# console-dat.net
KiCad netlist of a schematic drawn in EAGLE
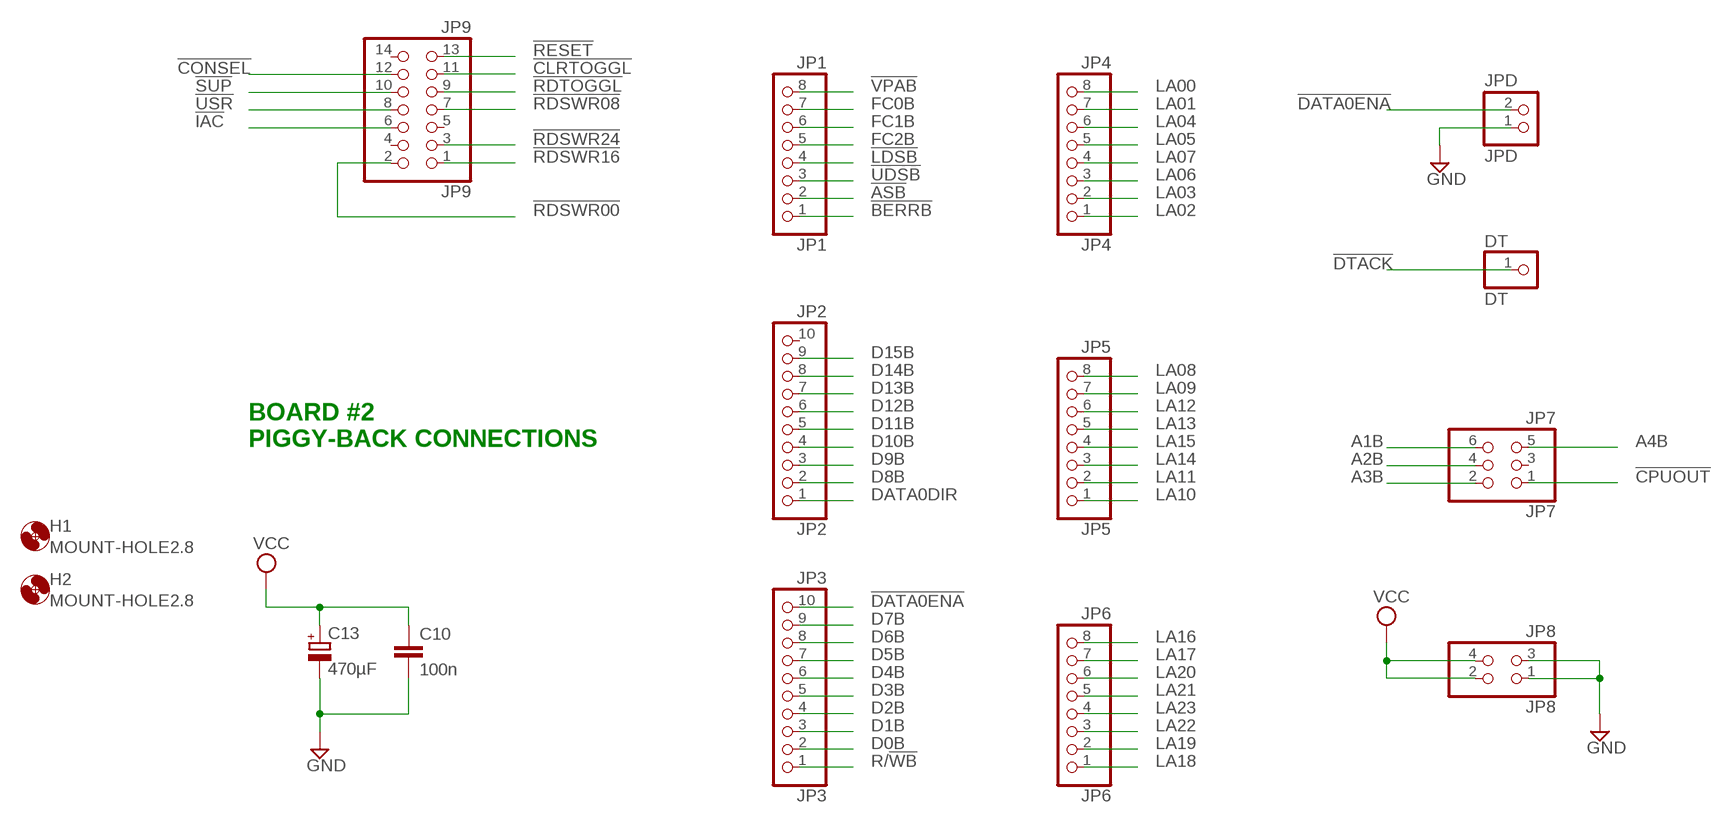
[diagram p0: schematic, sheet 1]
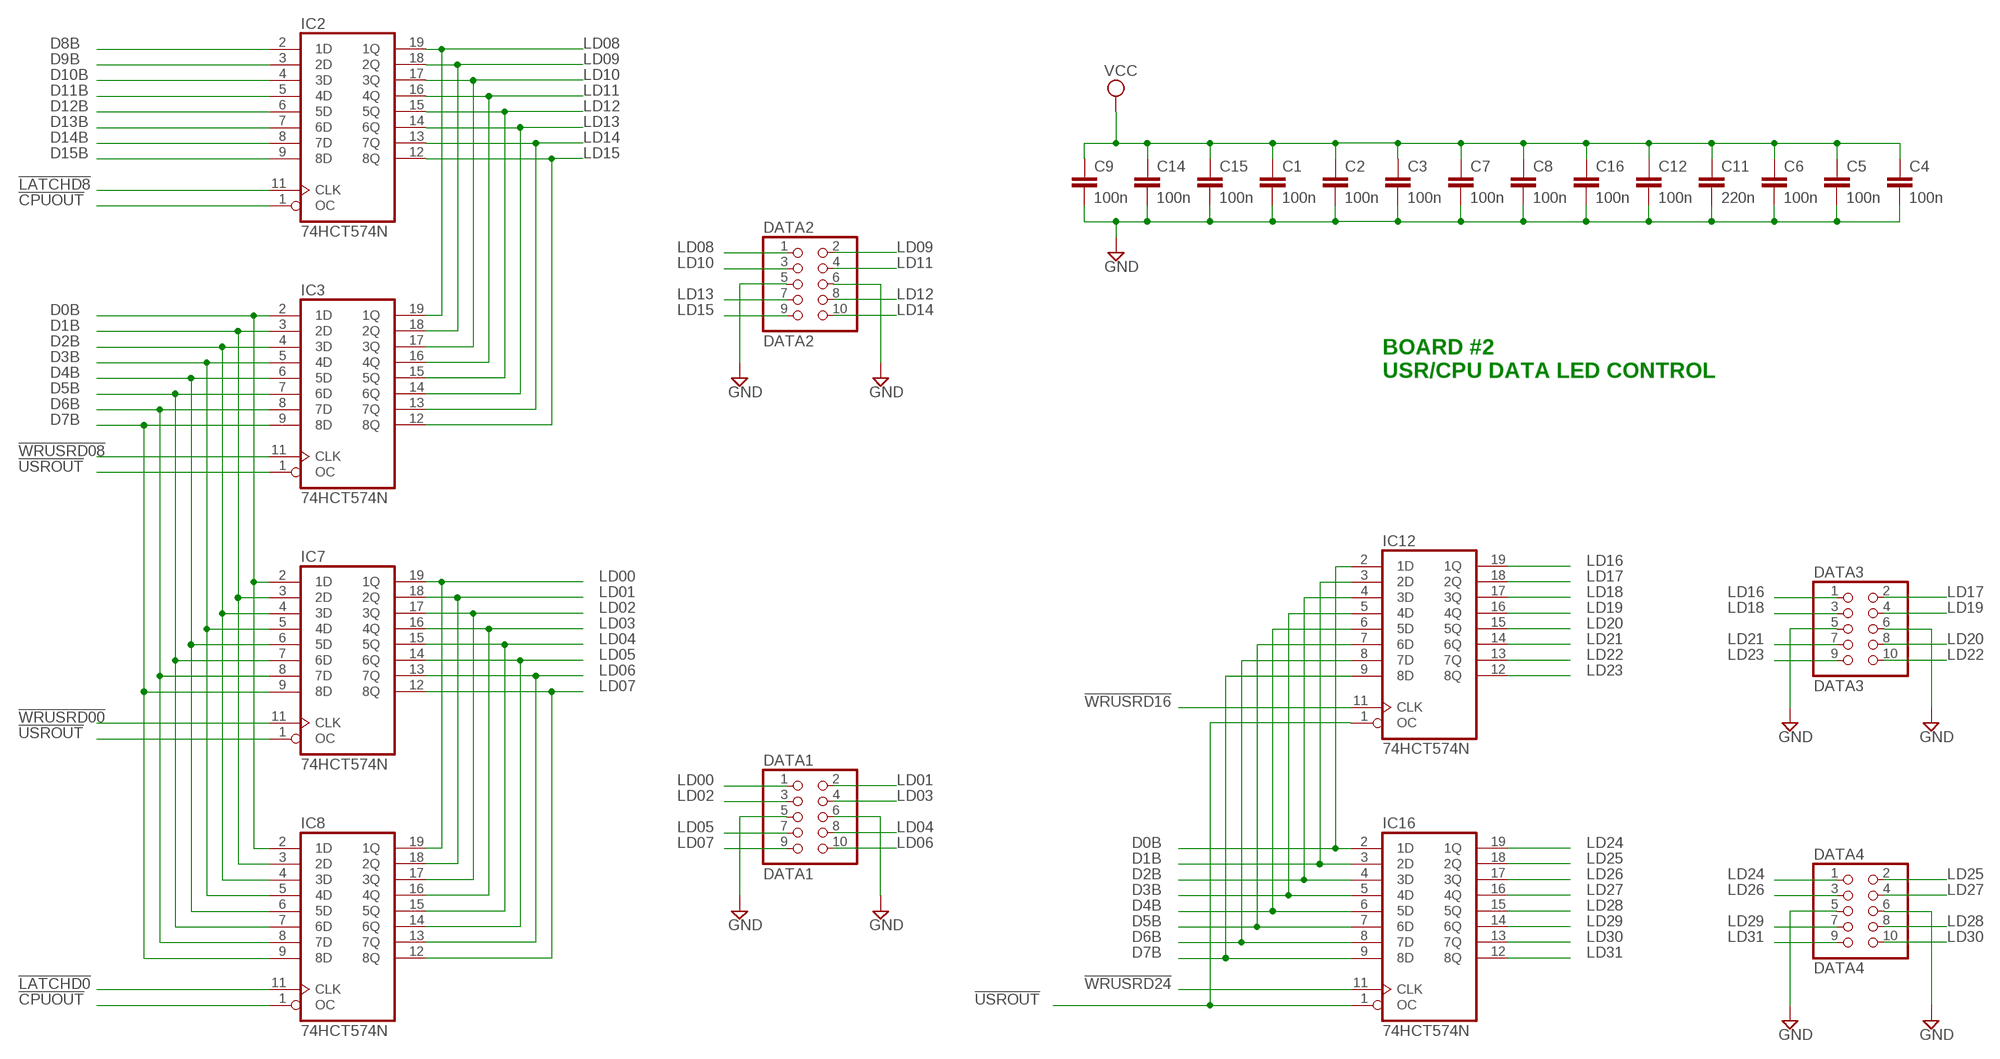
[diagram p1: schematic, sheet 2]
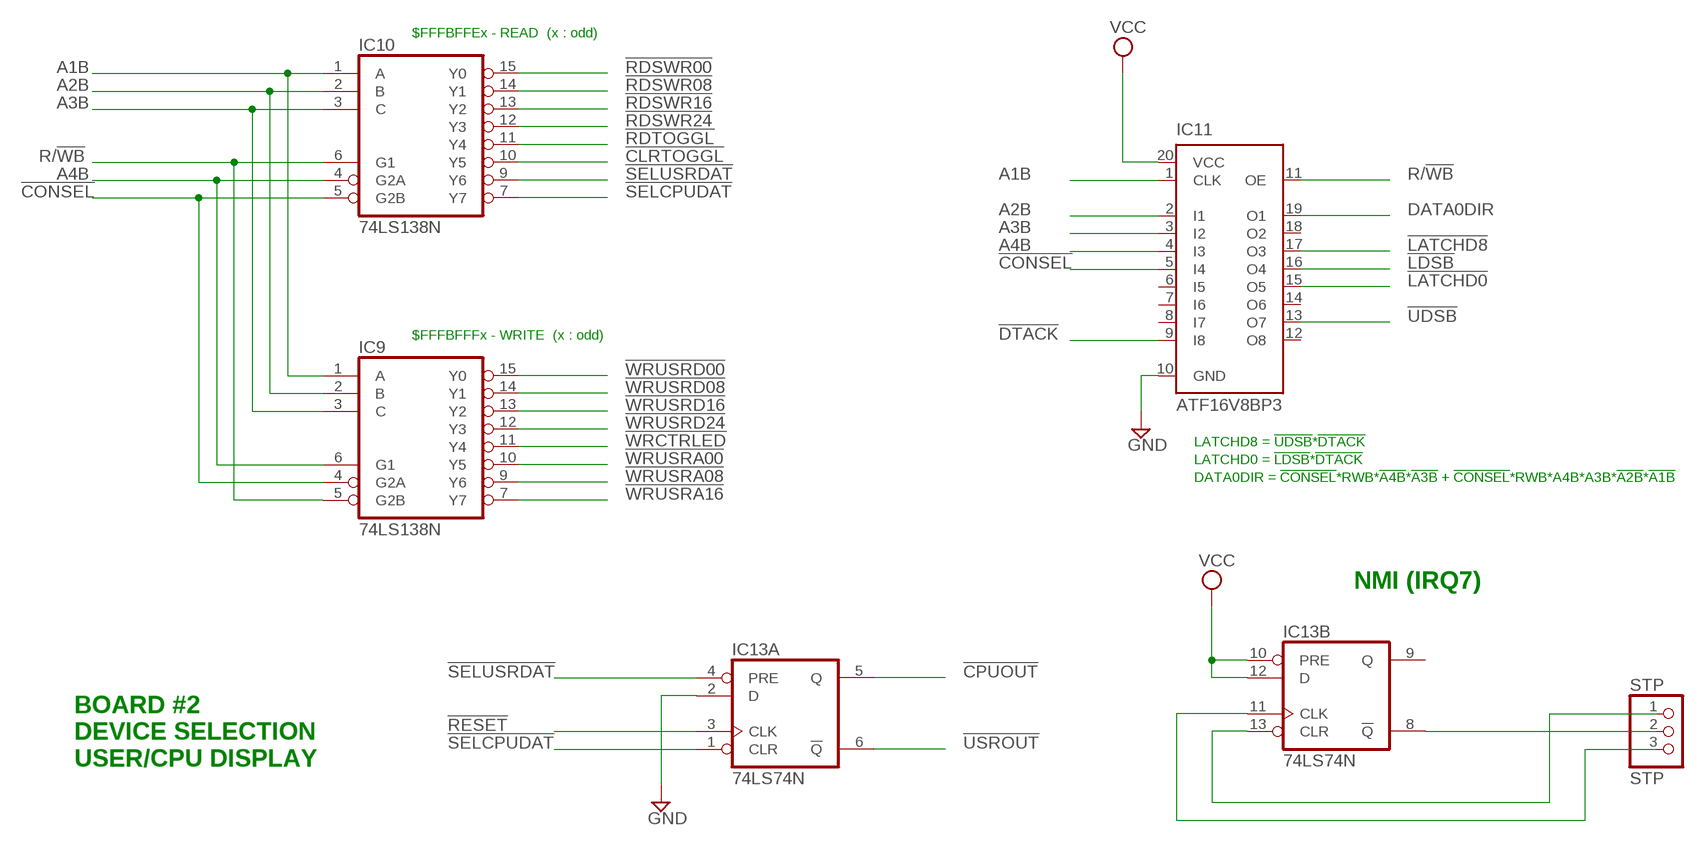
[diagram p2: schematic, sheet 3]
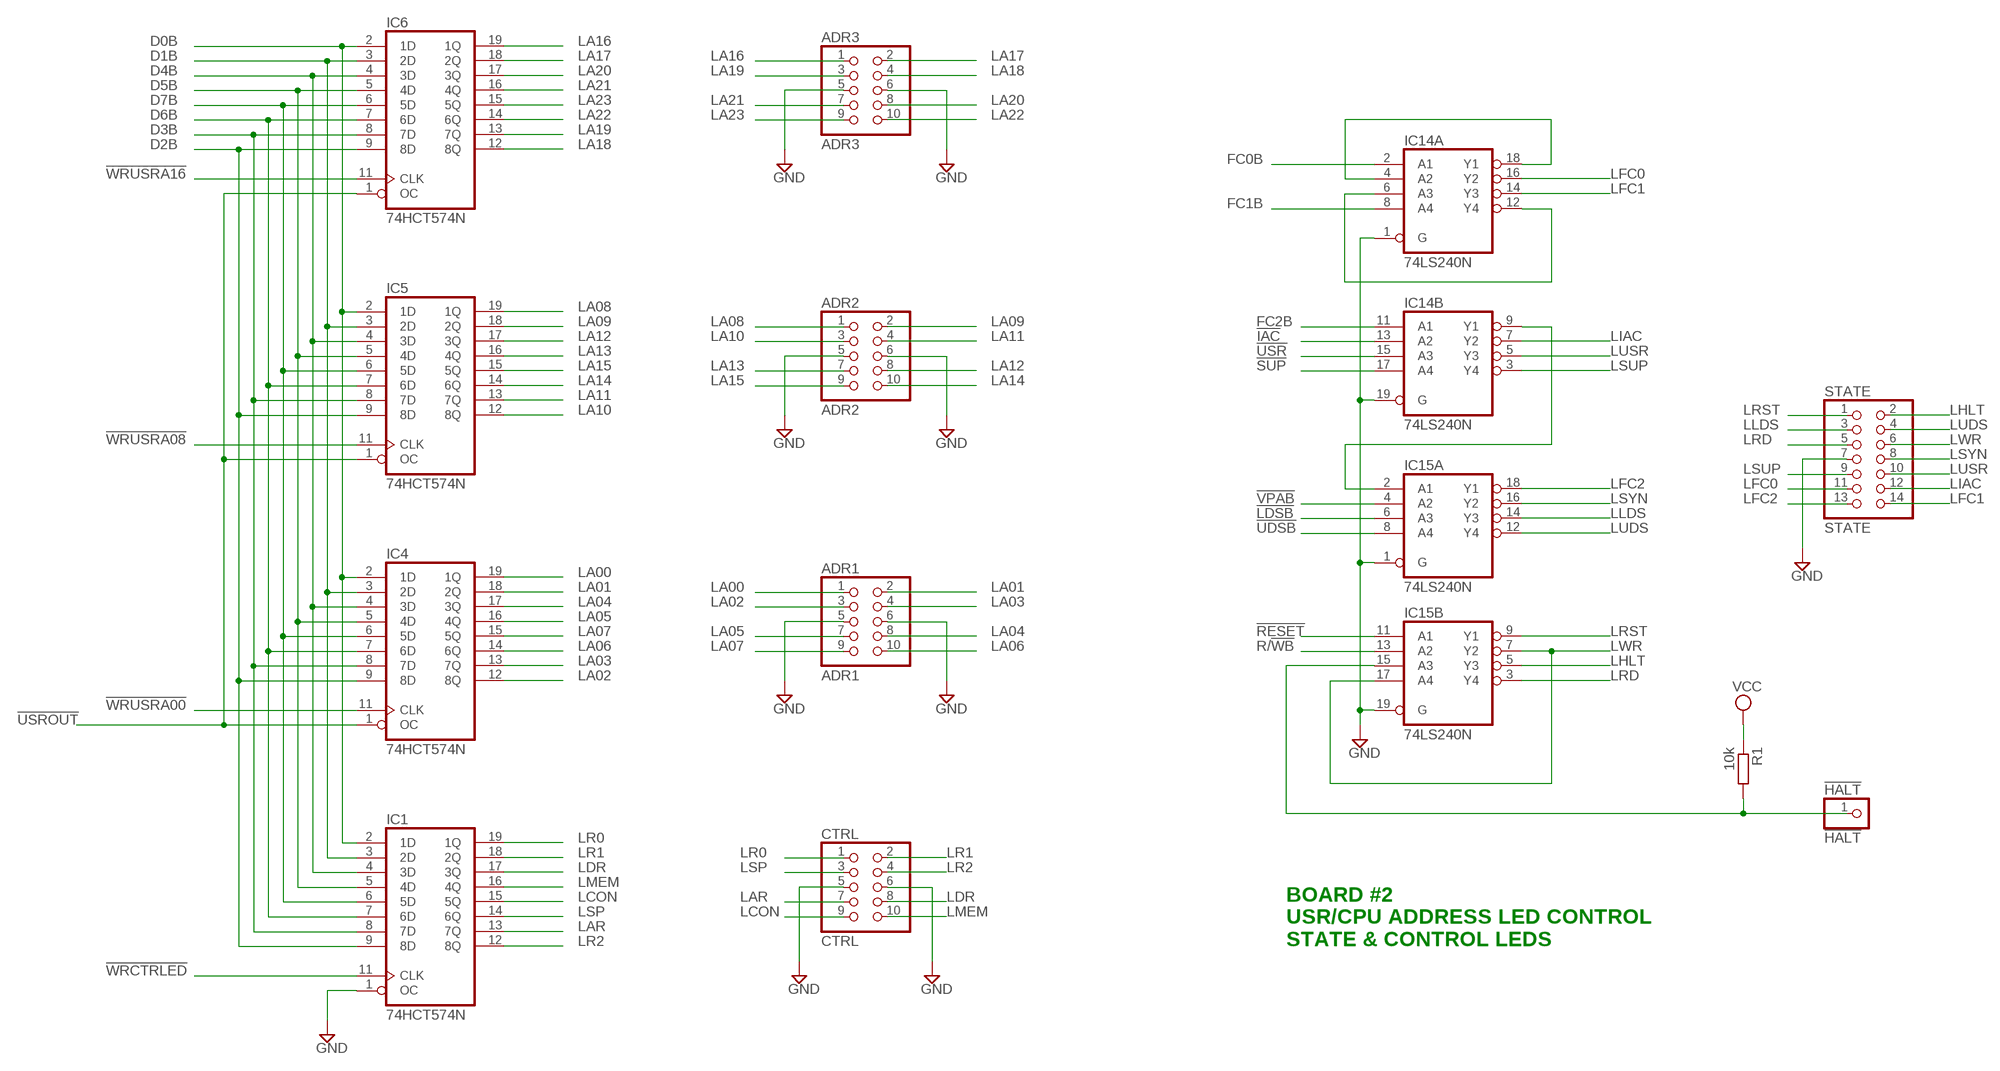
[diagram p3: schematic, sheet 4]

(export (version "E")
  (design (tool "Eeschema 10.0.6"))
  (components
    (comp (ref "IC9")
      (value "74LS138N")
      (footprint "eagle-import:DIL16")
      (libsource (lib "eagle-import") (part "74138NLS"))
    )
    (comp (ref "IC10")
      (value "74LS138N")
      (footprint "eagle-import:DIL16")
      (libsource (lib "eagle-import") (part "74138NLS"))
    )
    (comp (ref "IC11")
      (value "ATF16V8BP3")
      (footprint "eagle-import:DIL20")
      (fields (field (name "MPN") "ATF16V8CZ-15PU"))
      (libsource (lib "eagle-import") (part "ATF16V8BP3"))
    )
    (comp (ref "IC13")
      (value "74LS74N")
      (footprint "eagle-import:DIL14")
      (libsource (lib "eagle-import") (part "7474NLS"))
    )
    (comp (ref "STP")
      (value "STP")
      (footprint "eagle-import:1X03")
      (libsource (lib "eagle-import") (part "PINHD-1X3"))
    )
    (comp (ref "C10")
      (value "100n")
      (footprint "eagle-import:C025-024X044")
      (libsource (lib "eagle-import") (part "C-EU025-024X044"))
    )
    (comp (ref "C13")
      (value "470µF")
      (footprint "eagle-import:E2,5-7")
      (libsource (lib "eagle-import") (part "CPOL-EUE2.5-7"))
    )
    (comp (ref "DT")
      (value "DT")
      (footprint "eagle-import:1X01")
      (libsource (lib "eagle-import") (part "PINHD-1X1"))
    )
    (comp (ref "H1")
      (value "MOUNT-HOLE2.8")
      (footprint "eagle-import:2,8")
      (libsource (lib "eagle-import") (part "MOUNT-HOLE2.8"))
    )
    (comp (ref "H2")
      (value "MOUNT-HOLE2.8")
      (footprint "eagle-import:2,8")
      (libsource (lib "eagle-import") (part "MOUNT-HOLE2.8"))
    )
    (comp (ref "JP1")
      (value "JP1")
      (footprint "eagle-import:1X08")
      (libsource (lib "eagle-import") (part "PINHD-1X8"))
    )
    (comp (ref "JP2")
      (value "JP2")
      (footprint "eagle-import:1X10")
      (libsource (lib "eagle-import") (part "PINHD-1X10"))
    )
    (comp (ref "JP3")
      (value "JP3")
      (footprint "eagle-import:1X10")
      (libsource (lib "eagle-import") (part "PINHD-1X10"))
    )
    (comp (ref "JP4")
      (value "JP4")
      (footprint "eagle-import:1X08")
      (libsource (lib "eagle-import") (part "PINHD-1X8"))
    )
    (comp (ref "JP5")
      (value "JP5")
      (footprint "eagle-import:1X08")
      (libsource (lib "eagle-import") (part "PINHD-1X8"))
    )
    (comp (ref "JP6")
      (value "JP6")
      (footprint "eagle-import:1X08")
      (libsource (lib "eagle-import") (part "PINHD-1X8"))
    )
    (comp (ref "JP7")
      (value "JP7")
      (footprint "eagle-import:2X03")
      (libsource (lib "eagle-import") (part "PINHD-2X3"))
    )
    (comp (ref "JP8")
      (value "JP8")
      (footprint "eagle-import:2X02")
      (libsource (lib "eagle-import") (part "PINHD-2X2"))
    )
    (comp (ref "JP9")
      (value "JP9")
      (footprint "eagle-import:2X07")
      (libsource (lib "eagle-import") (part "PINHD-2X7"))
    )
    (comp (ref "JPD")
      (value "JPD")
      (footprint "eagle-import:1X02")
      (libsource (lib "eagle-import") (part "PINHD-1X2"))
    )
    (comp (ref "C1")
      (value "100n")
      (footprint "eagle-import:C025-024X044")
      (libsource (lib "eagle-import") (part "C-EU025-024X044"))
    )
    (comp (ref "C2")
      (value "100n")
      (footprint "eagle-import:C025-024X044")
      (libsource (lib "eagle-import") (part "C-EU025-024X044"))
    )
    (comp (ref "C3")
      (value "100n")
      (footprint "eagle-import:C025-024X044")
      (libsource (lib "eagle-import") (part "C-EU025-024X044"))
    )
    (comp (ref "C4")
      (value "100n")
      (footprint "eagle-import:C025-024X044")
      (libsource (lib "eagle-import") (part "C-EU025-024X044"))
    )
    (comp (ref "C5")
      (value "100n")
      (footprint "eagle-import:C025-024X044")
      (libsource (lib "eagle-import") (part "C-EU025-024X044"))
    )
    (comp (ref "C6")
      (value "100n")
      (footprint "eagle-import:C025-024X044")
      (libsource (lib "eagle-import") (part "C-EU025-024X044"))
    )
    (comp (ref "C7")
      (value "100n")
      (footprint "eagle-import:C025-024X044")
      (libsource (lib "eagle-import") (part "C-EU025-024X044"))
    )
    (comp (ref "C8")
      (value "100n")
      (footprint "eagle-import:C025-024X044")
      (libsource (lib "eagle-import") (part "C-EU025-024X044"))
    )
    (comp (ref "C9")
      (value "100n")
      (footprint "eagle-import:C025-024X044")
      (libsource (lib "eagle-import") (part "C-EU025-024X044"))
    )
    (comp (ref "C11")
      (value "220n")
      (footprint "eagle-import:C025-024X044")
      (libsource (lib "eagle-import") (part "C-EU025-024X044"))
    )
    (comp (ref "C12")
      (value "100n")
      (footprint "eagle-import:C025-024X044")
      (libsource (lib "eagle-import") (part "C-EU025-024X044"))
    )
    (comp (ref "C14")
      (value "100n")
      (footprint "eagle-import:C025-024X044")
      (libsource (lib "eagle-import") (part "C-EU025-024X044"))
    )
    (comp (ref "C15")
      (value "100n")
      (footprint "eagle-import:C025-024X044")
      (libsource (lib "eagle-import") (part "C-EU025-024X044"))
    )
    (comp (ref "C16")
      (value "100n")
      (footprint "eagle-import:C025-024X044")
      (libsource (lib "eagle-import") (part "C-EU025-024X044"))
    )
    (comp (ref "DATA1")
      (value "DATA1")
      (footprint "eagle-import:2X05")
      (libsource (lib "eagle-import") (part "PINHD-2X5"))
    )
    (comp (ref "DATA2")
      (value "DATA2")
      (footprint "eagle-import:2X05")
      (libsource (lib "eagle-import") (part "PINHD-2X5"))
    )
    (comp (ref "DATA3")
      (value "DATA3")
      (footprint "eagle-import:2X05")
      (libsource (lib "eagle-import") (part "PINHD-2X5"))
    )
    (comp (ref "DATA4")
      (value "DATA4")
      (footprint "eagle-import:2X05")
      (libsource (lib "eagle-import") (part "PINHD-2X5"))
    )
    (comp (ref "IC2")
      (value "74HCT574N")
      (footprint "eagle-import:DIL20")
      (libsource (lib "eagle-import") (part "74574NHCT"))
    )
    (comp (ref "IC3")
      (value "74HCT574N")
      (footprint "eagle-import:DIL20")
      (libsource (lib "eagle-import") (part "74574NHCT"))
    )
    (comp (ref "IC7")
      (value "74HCT574N")
      (footprint "eagle-import:DIL20")
      (libsource (lib "eagle-import") (part "74574NHCT"))
    )
    (comp (ref "IC8")
      (value "74HCT574N")
      (footprint "eagle-import:DIL20")
      (libsource (lib "eagle-import") (part "74574NHCT"))
    )
    (comp (ref "IC12")
      (value "74HCT574N")
      (footprint "eagle-import:DIL20")
      (libsource (lib "eagle-import") (part "74574NHCT"))
    )
    (comp (ref "IC16")
      (value "74HCT574N")
      (footprint "eagle-import:DIL20")
      (libsource (lib "eagle-import") (part "74574NHCT"))
    )
    (comp (ref "!HALT")
      (value "!HALT")
      (footprint "eagle-import:1X01")
      (libsource (lib "eagle-import") (part "PINHD-1X1"))
    )
    (comp (ref "ADR1")
      (value "ADR1")
      (footprint "eagle-import:2X05")
      (libsource (lib "eagle-import") (part "PINHD-2X5"))
    )
    (comp (ref "ADR2")
      (value "ADR2")
      (footprint "eagle-import:2X05")
      (libsource (lib "eagle-import") (part "PINHD-2X5"))
    )
    (comp (ref "ADR3")
      (value "ADR3")
      (footprint "eagle-import:2X05")
      (libsource (lib "eagle-import") (part "PINHD-2X5"))
    )
    (comp (ref "CTRL")
      (value "CTRL")
      (footprint "eagle-import:2X05")
      (libsource (lib "eagle-import") (part "PINHD-2X5"))
    )
    (comp (ref "IC1")
      (value "74HCT574N")
      (footprint "eagle-import:DIL20")
      (libsource (lib "eagle-import") (part "74574NHCT"))
    )
    (comp (ref "IC4")
      (value "74HCT574N")
      (footprint "eagle-import:DIL20")
      (libsource (lib "eagle-import") (part "74574NHCT"))
    )
    (comp (ref "IC5")
      (value "74HCT574N")
      (footprint "eagle-import:DIL20")
      (libsource (lib "eagle-import") (part "74574NHCT"))
    )
    (comp (ref "IC6")
      (value "74HCT574N")
      (footprint "eagle-import:DIL20")
      (libsource (lib "eagle-import") (part "74574NHCT"))
    )
    (comp (ref "IC14")
      (value "74LS240N")
      (footprint "eagle-import:DIL20")
      (libsource (lib "eagle-import") (part "74240NLS"))
    )
    (comp (ref "IC15")
      (value "74LS240N")
      (footprint "eagle-import:DIL20")
      (libsource (lib "eagle-import") (part "74240NLS"))
    )
    (comp (ref "R1")
      (value "10k")
      (footprint "eagle-import:0204_7")
      (libsource (lib "eagle-import") (part "R-EU_0204/7"))
    )
    (comp (ref "STATE")
      (value "STATE")
      (footprint "eagle-import:2X07")
      (libsource (lib "eagle-import") (part "PINHD-2X7"))
    )
  )
  (nets
    (net (code "1") (name "A1B") (class "Default")
      (node (ref "IC10") (pin "1") (pinfunction "A_1") (pintype "input"))
      (node (ref "IC11") (pin "1") (pinfunction "CLK_1") (pintype "input"))
      (node (ref "IC9") (pin "1") (pinfunction "A_1") (pintype "input"))
      (node (ref "JP7") (pin "6") (pinfunction "6_6") (pintype "passive"))
    )
    (net (code "2") (name "A2B") (class "Default")
      (node (ref "IC10") (pin "2") (pinfunction "B_2") (pintype "input"))
      (node (ref "IC11") (pin "2") (pinfunction "I1_2") (pintype "input"))
      (node (ref "IC9") (pin "2") (pinfunction "B_2") (pintype "input"))
      (node (ref "JP7") (pin "4") (pinfunction "4_4") (pintype "passive"))
    )
    (net (code "3") (name "A3B") (class "Default")
      (node (ref "IC10") (pin "3") (pinfunction "C_3") (pintype "input"))
      (node (ref "IC11") (pin "3") (pinfunction "I2_3") (pintype "input"))
      (node (ref "IC9") (pin "3") (pinfunction "C_3") (pintype "input"))
      (node (ref "JP7") (pin "2") (pinfunction "2_2") (pintype "passive"))
    )
    (net (code "4") (name "A4B") (class "Default")
      (node (ref "IC10") (pin "4") (pinfunction "G2A_4") (pintype "input"))
      (node (ref "IC11") (pin "4") (pinfunction "I3_4") (pintype "input"))
      (node (ref "IC9") (pin "6") (pinfunction "G1_6") (pintype "input"))
      (node (ref "JP7") (pin "5") (pinfunction "5_5") (pintype "passive"))
    )
    (net (code "5") (name "D0B") (class "Default")
      (node (ref "IC1") (pin "2") (pinfunction "1D_2") (pintype "input"))
      (node (ref "IC12") (pin "2") (pinfunction "1D_2") (pintype "input"))
      (node (ref "IC16") (pin "2") (pinfunction "1D_2") (pintype "input"))
      (node (ref "IC3") (pin "2") (pinfunction "1D_2") (pintype "input"))
      (node (ref "IC4") (pin "2") (pinfunction "1D_2") (pintype "input"))
      (node (ref "IC5") (pin "2") (pinfunction "1D_2") (pintype "input"))
      (node (ref "IC6") (pin "2") (pinfunction "1D_2") (pintype "input"))
      (node (ref "IC7") (pin "2") (pinfunction "1D_2") (pintype "input"))
      (node (ref "IC8") (pin "2") (pinfunction "1D_2") (pintype "input"))
      (node (ref "JP3") (pin "2") (pinfunction "2_2") (pintype "passive"))
    )
    (net (code "6") (name "D1B") (class "Default")
      (node (ref "IC1") (pin "3") (pinfunction "2D_3") (pintype "input"))
      (node (ref "IC12") (pin "3") (pinfunction "2D_3") (pintype "input"))
      (node (ref "IC16") (pin "3") (pinfunction "2D_3") (pintype "input"))
      (node (ref "IC3") (pin "3") (pinfunction "2D_3") (pintype "input"))
      (node (ref "IC4") (pin "3") (pinfunction "2D_3") (pintype "input"))
      (node (ref "IC5") (pin "3") (pinfunction "2D_3") (pintype "input"))
      (node (ref "IC6") (pin "3") (pinfunction "2D_3") (pintype "input"))
      (node (ref "IC7") (pin "3") (pinfunction "2D_3") (pintype "input"))
      (node (ref "IC8") (pin "3") (pinfunction "2D_3") (pintype "input"))
      (node (ref "JP3") (pin "3") (pinfunction "3_3") (pintype "passive"))
    )
    (net (code "7") (name "D2B") (class "Default")
      (node (ref "IC1") (pin "9") (pinfunction "8D_9") (pintype "input"))
      (node (ref "IC12") (pin "4") (pinfunction "3D_4") (pintype "input"))
      (node (ref "IC16") (pin "4") (pinfunction "3D_4") (pintype "input"))
      (node (ref "IC3") (pin "4") (pinfunction "3D_4") (pintype "input"))
      (node (ref "IC4") (pin "9") (pinfunction "8D_9") (pintype "input"))
      (node (ref "IC5") (pin "9") (pinfunction "8D_9") (pintype "input"))
      (node (ref "IC6") (pin "9") (pinfunction "8D_9") (pintype "input"))
      (node (ref "IC7") (pin "4") (pinfunction "3D_4") (pintype "input"))
      (node (ref "IC8") (pin "4") (pinfunction "3D_4") (pintype "input"))
      (node (ref "JP3") (pin "4") (pinfunction "4_4") (pintype "passive"))
    )
    (net (code "8") (name "D3B") (class "Default")
      (node (ref "IC1") (pin "8") (pinfunction "7D_8") (pintype "input"))
      (node (ref "IC12") (pin "5") (pinfunction "4D_5") (pintype "input"))
      (node (ref "IC16") (pin "5") (pinfunction "4D_5") (pintype "input"))
      (node (ref "IC3") (pin "5") (pinfunction "4D_5") (pintype "input"))
      (node (ref "IC4") (pin "8") (pinfunction "7D_8") (pintype "input"))
      (node (ref "IC5") (pin "8") (pinfunction "7D_8") (pintype "input"))
      (node (ref "IC6") (pin "8") (pinfunction "7D_8") (pintype "input"))
      (node (ref "IC7") (pin "5") (pinfunction "4D_5") (pintype "input"))
      (node (ref "IC8") (pin "5") (pinfunction "4D_5") (pintype "input"))
      (node (ref "JP3") (pin "5") (pinfunction "5_5") (pintype "passive"))
    )
    (net (code "9") (name "D4B") (class "Default")
      (node (ref "IC1") (pin "4") (pinfunction "3D_4") (pintype "input"))
      (node (ref "IC12") (pin "6") (pinfunction "5D_6") (pintype "input"))
      (node (ref "IC16") (pin "6") (pinfunction "5D_6") (pintype "input"))
      (node (ref "IC3") (pin "6") (pinfunction "5D_6") (pintype "input"))
      (node (ref "IC4") (pin "4") (pinfunction "3D_4") (pintype "input"))
      (node (ref "IC5") (pin "4") (pinfunction "3D_4") (pintype "input"))
      (node (ref "IC6") (pin "4") (pinfunction "3D_4") (pintype "input"))
      (node (ref "IC7") (pin "6") (pinfunction "5D_6") (pintype "input"))
      (node (ref "IC8") (pin "6") (pinfunction "5D_6") (pintype "input"))
      (node (ref "JP3") (pin "6") (pinfunction "6_6") (pintype "passive"))
    )
    (net (code "10") (name "D5B") (class "Default")
      (node (ref "IC1") (pin "5") (pinfunction "4D_5") (pintype "input"))
      (node (ref "IC12") (pin "7") (pinfunction "6D_7") (pintype "input"))
      (node (ref "IC16") (pin "7") (pinfunction "6D_7") (pintype "input"))
      (node (ref "IC3") (pin "7") (pinfunction "6D_7") (pintype "input"))
      (node (ref "IC4") (pin "5") (pinfunction "4D_5") (pintype "input"))
      (node (ref "IC5") (pin "5") (pinfunction "4D_5") (pintype "input"))
      (node (ref "IC6") (pin "5") (pinfunction "4D_5") (pintype "input"))
      (node (ref "IC7") (pin "7") (pinfunction "6D_7") (pintype "input"))
      (node (ref "IC8") (pin "7") (pinfunction "6D_7") (pintype "input"))
      (node (ref "JP3") (pin "7") (pinfunction "7_7") (pintype "passive"))
    )
    (net (code "11") (name "D6B") (class "Default")
      (node (ref "IC1") (pin "7") (pinfunction "6D_7") (pintype "input"))
      (node (ref "IC12") (pin "8") (pinfunction "7D_8") (pintype "input"))
      (node (ref "IC16") (pin "8") (pinfunction "7D_8") (pintype "input"))
      (node (ref "IC3") (pin "8") (pinfunction "7D_8") (pintype "input"))
      (node (ref "IC4") (pin "7") (pinfunction "6D_7") (pintype "input"))
      (node (ref "IC5") (pin "7") (pinfunction "6D_7") (pintype "input"))
      (node (ref "IC6") (pin "7") (pinfunction "6D_7") (pintype "input"))
      (node (ref "IC7") (pin "8") (pinfunction "7D_8") (pintype "input"))
      (node (ref "IC8") (pin "8") (pinfunction "7D_8") (pintype "input"))
      (node (ref "JP3") (pin "8") (pinfunction "8_8") (pintype "passive"))
    )
    (net (code "12") (name "D7B") (class "Default")
      (node (ref "IC1") (pin "6") (pinfunction "5D_6") (pintype "input"))
      (node (ref "IC12") (pin "9") (pinfunction "8D_9") (pintype "input"))
      (node (ref "IC16") (pin "9") (pinfunction "8D_9") (pintype "input"))
      (node (ref "IC3") (pin "9") (pinfunction "8D_9") (pintype "input"))
      (node (ref "IC4") (pin "6") (pinfunction "5D_6") (pintype "input"))
      (node (ref "IC5") (pin "6") (pinfunction "5D_6") (pintype "input"))
      (node (ref "IC6") (pin "6") (pinfunction "5D_6") (pintype "input"))
      (node (ref "IC7") (pin "9") (pinfunction "8D_9") (pintype "input"))
      (node (ref "IC8") (pin "9") (pinfunction "8D_9") (pintype "input"))
      (node (ref "JP3") (pin "9") (pinfunction "9_9") (pintype "passive"))
    )
    (net (code "13") (name "D8B") (class "Default")
      (node (ref "IC2") (pin "2") (pinfunction "1D_2") (pintype "input"))
      (node (ref "JP2") (pin "2") (pinfunction "2_2") (pintype "passive"))
    )
    (net (code "14") (name "D9B") (class "Default")
      (node (ref "IC2") (pin "3") (pinfunction "2D_3") (pintype "input"))
      (node (ref "JP2") (pin "3") (pinfunction "3_3") (pintype "passive"))
    )
    (net (code "15") (name "D10B") (class "Default")
      (node (ref "IC2") (pin "4") (pinfunction "3D_4") (pintype "input"))
      (node (ref "JP2") (pin "4") (pinfunction "4_4") (pintype "passive"))
    )
    (net (code "16") (name "D11B") (class "Default")
      (node (ref "IC2") (pin "5") (pinfunction "4D_5") (pintype "input"))
      (node (ref "JP2") (pin "5") (pinfunction "5_5") (pintype "passive"))
    )
    (net (code "17") (name "D12B") (class "Default")
      (node (ref "IC2") (pin "6") (pinfunction "5D_6") (pintype "input"))
      (node (ref "JP2") (pin "6") (pinfunction "6_6") (pintype "passive"))
    )
    (net (code "18") (name "D13B") (class "Default")
      (node (ref "IC2") (pin "7") (pinfunction "6D_7") (pintype "input"))
      (node (ref "JP2") (pin "7") (pinfunction "7_7") (pintype "passive"))
    )
    (net (code "19") (name "D14B") (class "Default")
      (node (ref "IC2") (pin "8") (pinfunction "7D_8") (pintype "input"))
      (node (ref "JP2") (pin "8") (pinfunction "8_8") (pintype "passive"))
    )
    (net (code "20") (name "D15B") (class "Default")
      (node (ref "IC2") (pin "9") (pinfunction "8D_9") (pintype "input"))
      (node (ref "JP2") (pin "9") (pinfunction "9_9") (pintype "passive"))
    )
    (net (code "21") (name "DATA0DIR") (class "Default")
      (node (ref "IC11") (pin "19") (pinfunction "O1_19") (pintype "output"))
      (node (ref "JP2") (pin "1") (pinfunction "1_1") (pintype "passive"))
    )
    (net (code "22") (name "FC0B") (class "Default")
      (node (ref "IC14") (pin "2") (pinfunction "A1_2") (pintype "input"))
      (node (ref "JP1") (pin "7") (pinfunction "7_7") (pintype "passive"))
    )
    (net (code "23") (name "FC1B") (class "Default")
      (node (ref "IC14") (pin "8") (pinfunction "A4_8") (pintype "input"))
      (node (ref "JP1") (pin "6") (pinfunction "6_6") (pintype "passive"))
    )
    (net (code "24") (name "FC2B") (class "Default")
      (node (ref "IC14") (pin "11") (pinfunction "A1_11") (pintype "input"))
      (node (ref "JP1") (pin "5") (pinfunction "5_5") (pintype "passive"))
    )
    (net (code "25") (name "GND") (class "Default")
      (node (ref "ADR1") (pin "5") (pinfunction "5_5") (pintype "passive"))
      (node (ref "ADR1") (pin "6") (pinfunction "6_6") (pintype "passive"))
      (node (ref "ADR2") (pin "5") (pinfunction "5_5") (pintype "passive"))
      (node (ref "ADR2") (pin "6") (pinfunction "6_6") (pintype "passive"))
      (node (ref "ADR3") (pin "5") (pinfunction "5_5") (pintype "passive"))
      (node (ref "ADR3") (pin "6") (pinfunction "6_6") (pintype "passive"))
      (node (ref "C1") (pin "2") (pinfunction "2_2") (pintype "passive"))
      (node (ref "C10") (pin "2") (pinfunction "2_2") (pintype "passive"))
      (node (ref "C11") (pin "2") (pinfunction "2_2") (pintype "passive"))
      (node (ref "C12") (pin "2") (pinfunction "2_2") (pintype "passive"))
      (node (ref "C13") (pin "-") (pinfunction "-_-") (pintype "passive"))
      (node (ref "C14") (pin "2") (pinfunction "2_2") (pintype "passive"))
      (node (ref "C15") (pin "2") (pinfunction "2_2") (pintype "passive"))
      (node (ref "C16") (pin "2") (pinfunction "2_2") (pintype "passive"))
      (node (ref "C2") (pin "2") (pinfunction "2_2") (pintype "passive"))
      (node (ref "C3") (pin "2") (pinfunction "2_2") (pintype "passive"))
      (node (ref "C4") (pin "2") (pinfunction "2_2") (pintype "passive"))
      (node (ref "C5") (pin "2") (pinfunction "2_2") (pintype "passive"))
      (node (ref "C6") (pin "2") (pinfunction "2_2") (pintype "passive"))
      (node (ref "C7") (pin "2") (pinfunction "2_2") (pintype "passive"))
      (node (ref "C8") (pin "2") (pinfunction "2_2") (pintype "passive"))
      (node (ref "C9") (pin "2") (pinfunction "2_2") (pintype "passive"))
      (node (ref "CTRL") (pin "5") (pinfunction "5_5") (pintype "passive"))
      (node (ref "CTRL") (pin "6") (pinfunction "6_6") (pintype "passive"))
      (node (ref "DATA1") (pin "5") (pinfunction "5_5") (pintype "passive"))
      (node (ref "DATA1") (pin "6") (pinfunction "6_6") (pintype "passive"))
      (node (ref "DATA2") (pin "5") (pinfunction "5_5") (pintype "passive"))
      (node (ref "DATA2") (pin "6") (pinfunction "6_6") (pintype "passive"))
      (node (ref "DATA3") (pin "5") (pinfunction "5_5") (pintype "passive"))
      (node (ref "DATA3") (pin "6") (pinfunction "6_6") (pintype "passive"))
      (node (ref "DATA4") (pin "5") (pinfunction "5_5") (pintype "passive"))
      (node (ref "DATA4") (pin "6") (pinfunction "6_6") (pintype "passive"))
      (node (ref "IC1") (pin "1") (pinfunction "OC_1") (pintype "input"))
      (node (ref "IC11") (pin "10") (pinfunction "GND_10") (pintype "power_in"))
      (node (ref "IC13") (pin "2") (pinfunction "D_2") (pintype "input"))
      (node (ref "IC14") (pin "1") (pinfunction "G_1") (pintype "input"))
      (node (ref "IC14") (pin "19") (pinfunction "G_19") (pintype "input"))
      (node (ref "IC15") (pin "1") (pinfunction "G_1") (pintype "input"))
      (node (ref "IC15") (pin "19") (pinfunction "G_19") (pintype "input"))
      (node (ref "JP8") (pin "1") (pinfunction "1_1") (pintype "passive"))
      (node (ref "JP8") (pin "3") (pinfunction "3_3") (pintype "passive"))
      (node (ref "JPD") (pin "1") (pinfunction "1_1") (pintype "passive"))
      (node (ref "STATE") (pin "7") (pinfunction "7_7") (pintype "passive"))
    )
    (net (code "26") (name "LA00") (class "Default")
      (node (ref "ADR1") (pin "1") (pinfunction "1_1") (pintype "passive"))
      (node (ref "IC4") (pin "19") (pinfunction "1Q_19") (pintype "tri_state"))
      (node (ref "JP4") (pin "8") (pinfunction "8_8") (pintype "passive"))
    )
    (net (code "27") (name "LA01") (class "Default")
      (node (ref "ADR1") (pin "2") (pinfunction "2_2") (pintype "passive"))
      (node (ref "IC4") (pin "18") (pinfunction "2Q_18") (pintype "tri_state"))
      (node (ref "JP4") (pin "7") (pinfunction "7_7") (pintype "passive"))
    )
    (net (code "28") (name "LA02") (class "Default")
      (node (ref "ADR1") (pin "3") (pinfunction "3_3") (pintype "passive"))
      (node (ref "IC4") (pin "12") (pinfunction "8Q_12") (pintype "tri_state"))
      (node (ref "JP4") (pin "1") (pinfunction "1_1") (pintype "passive"))
    )
    (net (code "29") (name "LA03") (class "Default")
      (node (ref "ADR1") (pin "4") (pinfunction "4_4") (pintype "passive"))
      (node (ref "IC4") (pin "13") (pinfunction "7Q_13") (pintype "tri_state"))
      (node (ref "JP4") (pin "2") (pinfunction "2_2") (pintype "passive"))
    )
    (net (code "30") (name "LA04") (class "Default")
      (node (ref "ADR1") (pin "8") (pinfunction "8_8") (pintype "passive"))
      (node (ref "IC4") (pin "17") (pinfunction "3Q_17") (pintype "tri_state"))
      (node (ref "JP4") (pin "6") (pinfunction "6_6") (pintype "passive"))
    )
    (net (code "31") (name "LA05") (class "Default")
      (node (ref "ADR1") (pin "7") (pinfunction "7_7") (pintype "passive"))
      (node (ref "IC4") (pin "16") (pinfunction "4Q_16") (pintype "tri_state"))
      (node (ref "JP4") (pin "5") (pinfunction "5_5") (pintype "passive"))
    )
    (net (code "32") (name "LA06") (class "Default")
      (node (ref "ADR1") (pin "10") (pinfunction "10_10") (pintype "passive"))
      (node (ref "IC4") (pin "14") (pinfunction "6Q_14") (pintype "tri_state"))
      (node (ref "JP4") (pin "3") (pinfunction "3_3") (pintype "passive"))
    )
    (net (code "33") (name "LA07") (class "Default")
      (node (ref "ADR1") (pin "9") (pinfunction "9_9") (pintype "passive"))
      (node (ref "IC4") (pin "15") (pinfunction "5Q_15") (pintype "tri_state"))
      (node (ref "JP4") (pin "4") (pinfunction "4_4") (pintype "passive"))
    )
    (net (code "34") (name "LA08") (class "Default")
      (node (ref "ADR2") (pin "1") (pinfunction "1_1") (pintype "passive"))
      (node (ref "IC5") (pin "19") (pinfunction "1Q_19") (pintype "tri_state"))
      (node (ref "JP5") (pin "8") (pinfunction "8_8") (pintype "passive"))
    )
    (net (code "35") (name "LA09") (class "Default")
      (node (ref "ADR2") (pin "2") (pinfunction "2_2") (pintype "passive"))
      (node (ref "IC5") (pin "18") (pinfunction "2Q_18") (pintype "tri_state"))
      (node (ref "JP5") (pin "7") (pinfunction "7_7") (pintype "passive"))
    )
    (net (code "36") (name "LA10") (class "Default")
      (node (ref "ADR2") (pin "3") (pinfunction "3_3") (pintype "passive"))
      (node (ref "IC5") (pin "12") (pinfunction "8Q_12") (pintype "tri_state"))
      (node (ref "JP5") (pin "1") (pinfunction "1_1") (pintype "passive"))
    )
    (net (code "37") (name "LA11") (class "Default")
      (node (ref "ADR2") (pin "4") (pinfunction "4_4") (pintype "passive"))
      (node (ref "IC5") (pin "13") (pinfunction "7Q_13") (pintype "tri_state"))
      (node (ref "JP5") (pin "2") (pinfunction "2_2") (pintype "passive"))
    )
    (net (code "38") (name "LA12") (class "Default")
      (node (ref "ADR2") (pin "8") (pinfunction "8_8") (pintype "passive"))
      (node (ref "IC5") (pin "17") (pinfunction "3Q_17") (pintype "tri_state"))
      (node (ref "JP5") (pin "6") (pinfunction "6_6") (pintype "passive"))
    )
    (net (code "39") (name "LA13") (class "Default")
      (node (ref "ADR2") (pin "7") (pinfunction "7_7") (pintype "passive"))
      (node (ref "IC5") (pin "16") (pinfunction "4Q_16") (pintype "tri_state"))
      (node (ref "JP5") (pin "5") (pinfunction "5_5") (pintype "passive"))
    )
    (net (code "40") (name "LA14") (class "Default")
      (node (ref "ADR2") (pin "10") (pinfunction "10_10") (pintype "passive"))
      (node (ref "IC5") (pin "14") (pinfunction "6Q_14") (pintype "tri_state"))
      (node (ref "JP5") (pin "3") (pinfunction "3_3") (pintype "passive"))
    )
    (net (code "41") (name "LA15") (class "Default")
      (node (ref "ADR2") (pin "9") (pinfunction "9_9") (pintype "passive"))
      (node (ref "IC5") (pin "15") (pinfunction "5Q_15") (pintype "tri_state"))
      (node (ref "JP5") (pin "4") (pinfunction "4_4") (pintype "passive"))
    )
    (net (code "42") (name "LA16") (class "Default")
      (node (ref "ADR3") (pin "1") (pinfunction "1_1") (pintype "passive"))
      (node (ref "IC6") (pin "19") (pinfunction "1Q_19") (pintype "tri_state"))
      (node (ref "JP6") (pin "8") (pinfunction "8_8") (pintype "passive"))
    )
    (net (code "43") (name "LA17") (class "Default")
      (node (ref "ADR3") (pin "2") (pinfunction "2_2") (pintype "passive"))
      (node (ref "IC6") (pin "18") (pinfunction "2Q_18") (pintype "tri_state"))
      (node (ref "JP6") (pin "7") (pinfunction "7_7") (pintype "passive"))
    )
    (net (code "44") (name "LA18") (class "Default")
      (node (ref "ADR3") (pin "4") (pinfunction "4_4") (pintype "passive"))
      (node (ref "IC6") (pin "12") (pinfunction "8Q_12") (pintype "tri_state"))
      (node (ref "JP6") (pin "1") (pinfunction "1_1") (pintype "passive"))
    )
    (net (code "45") (name "LA19") (class "Default")
      (node (ref "ADR3") (pin "3") (pinfunction "3_3") (pintype "passive"))
      (node (ref "IC6") (pin "13") (pinfunction "7Q_13") (pintype "tri_state"))
      (node (ref "JP6") (pin "2") (pinfunction "2_2") (pintype "passive"))
    )
    (net (code "46") (name "LA20") (class "Default")
      (node (ref "ADR3") (pin "8") (pinfunction "8_8") (pintype "passive"))
      (node (ref "IC6") (pin "17") (pinfunction "3Q_17") (pintype "tri_state"))
      (node (ref "JP6") (pin "6") (pinfunction "6_6") (pintype "passive"))
    )
    (net (code "47") (name "LA21") (class "Default")
      (node (ref "ADR3") (pin "7") (pinfunction "7_7") (pintype "passive"))
      (node (ref "IC6") (pin "16") (pinfunction "4Q_16") (pintype "tri_state"))
      (node (ref "JP6") (pin "5") (pinfunction "5_5") (pintype "passive"))
    )
    (net (code "48") (name "LA22") (class "Default")
      (node (ref "ADR3") (pin "10") (pinfunction "10_10") (pintype "passive"))
      (node (ref "IC6") (pin "14") (pinfunction "6Q_14") (pintype "tri_state"))
      (node (ref "JP6") (pin "3") (pinfunction "3_3") (pintype "passive"))
    )
    (net (code "49") (name "LA23") (class "Default")
      (node (ref "ADR3") (pin "9") (pinfunction "9_9") (pintype "passive"))
      (node (ref "IC6") (pin "15") (pinfunction "5Q_15") (pintype "tri_state"))
      (node (ref "JP6") (pin "4") (pinfunction "4_4") (pintype "passive"))
    )
    (net (code "50") (name "LAR") (class "Default")
      (node (ref "CTRL") (pin "7") (pinfunction "7_7") (pintype "passive"))
      (node (ref "IC1") (pin "13") (pinfunction "7Q_13") (pintype "tri_state"))
    )
    (net (code "51") (name "LCON") (class "Default")
      (node (ref "CTRL") (pin "9") (pinfunction "9_9") (pintype "passive"))
      (node (ref "IC1") (pin "15") (pinfunction "5Q_15") (pintype "tri_state"))
    )
    (net (code "52") (name "LD00") (class "Default")
      (node (ref "DATA1") (pin "1") (pinfunction "1_1") (pintype "passive"))
      (node (ref "IC7") (pin "19") (pinfunction "1Q_19") (pintype "tri_state"))
      (node (ref "IC8") (pin "19") (pinfunction "1Q_19") (pintype "tri_state"))
    )
    (net (code "53") (name "LD01") (class "Default")
      (node (ref "DATA1") (pin "2") (pinfunction "2_2") (pintype "passive"))
      (node (ref "IC7") (pin "18") (pinfunction "2Q_18") (pintype "tri_state"))
      (node (ref "IC8") (pin "18") (pinfunction "2Q_18") (pintype "tri_state"))
    )
    (net (code "54") (name "LD02") (class "Default")
      (node (ref "DATA1") (pin "3") (pinfunction "3_3") (pintype "passive"))
      (node (ref "IC7") (pin "17") (pinfunction "3Q_17") (pintype "tri_state"))
      (node (ref "IC8") (pin "17") (pinfunction "3Q_17") (pintype "tri_state"))
    )
    (net (code "55") (name "LD03") (class "Default")
      (node (ref "DATA1") (pin "4") (pinfunction "4_4") (pintype "passive"))
      (node (ref "IC7") (pin "16") (pinfunction "4Q_16") (pintype "tri_state"))
      (node (ref "IC8") (pin "16") (pinfunction "4Q_16") (pintype "tri_state"))
    )
    (net (code "56") (name "LD04") (class "Default")
      (node (ref "DATA1") (pin "8") (pinfunction "8_8") (pintype "passive"))
      (node (ref "IC7") (pin "15") (pinfunction "5Q_15") (pintype "tri_state"))
      (node (ref "IC8") (pin "15") (pinfunction "5Q_15") (pintype "tri_state"))
    )
    (net (code "57") (name "LD05") (class "Default")
      (node (ref "DATA1") (pin "7") (pinfunction "7_7") (pintype "passive"))
      (node (ref "IC7") (pin "14") (pinfunction "6Q_14") (pintype "tri_state"))
      (node (ref "IC8") (pin "14") (pinfunction "6Q_14") (pintype "tri_state"))
    )
    (net (code "58") (name "LD06") (class "Default")
      (node (ref "DATA1") (pin "10") (pinfunction "10_10") (pintype "passive"))
      (node (ref "IC7") (pin "13") (pinfunction "7Q_13") (pintype "tri_state"))
      (node (ref "IC8") (pin "13") (pinfunction "7Q_13") (pintype "tri_state"))
    )
    (net (code "59") (name "LD07") (class "Default")
      (node (ref "DATA1") (pin "9") (pinfunction "9_9") (pintype "passive"))
      (node (ref "IC7") (pin "12") (pinfunction "8Q_12") (pintype "tri_state"))
      (node (ref "IC8") (pin "12") (pinfunction "8Q_12") (pintype "tri_state"))
    )
    (net (code "60") (name "LD08") (class "Default")
      (node (ref "DATA2") (pin "1") (pinfunction "1_1") (pintype "passive"))
      (node (ref "IC2") (pin "19") (pinfunction "1Q_19") (pintype "tri_state"))
      (node (ref "IC3") (pin "19") (pinfunction "1Q_19") (pintype "tri_state"))
    )
    (net (code "61") (name "LD09") (class "Default")
      (node (ref "DATA2") (pin "2") (pinfunction "2_2") (pintype "passive"))
      (node (ref "IC2") (pin "18") (pinfunction "2Q_18") (pintype "tri_state"))
      (node (ref "IC3") (pin "18") (pinfunction "2Q_18") (pintype "tri_state"))
    )
    (net (code "62") (name "LD10") (class "Default")
      (node (ref "DATA2") (pin "3") (pinfunction "3_3") (pintype "passive"))
      (node (ref "IC2") (pin "17") (pinfunction "3Q_17") (pintype "tri_state"))
      (node (ref "IC3") (pin "17") (pinfunction "3Q_17") (pintype "tri_state"))
    )
    (net (code "63") (name "LD11") (class "Default")
      (node (ref "DATA2") (pin "4") (pinfunction "4_4") (pintype "passive"))
      (node (ref "IC2") (pin "16") (pinfunction "4Q_16") (pintype "tri_state"))
      (node (ref "IC3") (pin "16") (pinfunction "4Q_16") (pintype "tri_state"))
    )
    (net (code "64") (name "LD12") (class "Default")
      (node (ref "DATA2") (pin "8") (pinfunction "8_8") (pintype "passive"))
      (node (ref "IC2") (pin "15") (pinfunction "5Q_15") (pintype "tri_state"))
      (node (ref "IC3") (pin "15") (pinfunction "5Q_15") (pintype "tri_state"))
    )
    (net (code "65") (name "LD13") (class "Default")
      (node (ref "DATA2") (pin "7") (pinfunction "7_7") (pintype "passive"))
      (node (ref "IC2") (pin "14") (pinfunction "6Q_14") (pintype "tri_state"))
      (node (ref "IC3") (pin "14") (pinfunction "6Q_14") (pintype "tri_state"))
    )
    (net (code "66") (name "LD14") (class "Default")
      (node (ref "DATA2") (pin "10") (pinfunction "10_10") (pintype "passive"))
      (node (ref "IC2") (pin "13") (pinfunction "7Q_13") (pintype "tri_state"))
      (node (ref "IC3") (pin "13") (pinfunction "7Q_13") (pintype "tri_state"))
    )
    (net (code "67") (name "LD15") (class "Default")
      (node (ref "DATA2") (pin "9") (pinfunction "9_9") (pintype "passive"))
      (node (ref "IC2") (pin "12") (pinfunction "8Q_12") (pintype "tri_state"))
      (node (ref "IC3") (pin "12") (pinfunction "8Q_12") (pintype "tri_state"))
    )
    (net (code "68") (name "LD16") (class "Default")
      (node (ref "DATA3") (pin "1") (pinfunction "1_1") (pintype "passive"))
      (node (ref "IC12") (pin "19") (pinfunction "1Q_19") (pintype "tri_state"))
    )
    (net (code "69") (name "LD17") (class "Default")
      (node (ref "DATA3") (pin "2") (pinfunction "2_2") (pintype "passive"))
      (node (ref "IC12") (pin "18") (pinfunction "2Q_18") (pintype "tri_state"))
    )
    (net (code "70") (name "LD18") (class "Default")
      (node (ref "DATA3") (pin "3") (pinfunction "3_3") (pintype "passive"))
      (node (ref "IC12") (pin "17") (pinfunction "3Q_17") (pintype "tri_state"))
    )
    (net (code "71") (name "LD19") (class "Default")
      (node (ref "DATA3") (pin "4") (pinfunction "4_4") (pintype "passive"))
      (node (ref "IC12") (pin "16") (pinfunction "4Q_16") (pintype "tri_state"))
    )
    (net (code "72") (name "LD20") (class "Default")
      (node (ref "DATA3") (pin "8") (pinfunction "8_8") (pintype "passive"))
      (node (ref "IC12") (pin "15") (pinfunction "5Q_15") (pintype "tri_state"))
    )
    (net (code "73") (name "LD21") (class "Default")
      (node (ref "DATA3") (pin "7") (pinfunction "7_7") (pintype "passive"))
      (node (ref "IC12") (pin "14") (pinfunction "6Q_14") (pintype "tri_state"))
    )
    (net (code "74") (name "LD22") (class "Default")
      (node (ref "DATA3") (pin "10") (pinfunction "10_10") (pintype "passive"))
      (node (ref "IC12") (pin "13") (pinfunction "7Q_13") (pintype "tri_state"))
    )
    (net (code "75") (name "LD23") (class "Default")
      (node (ref "DATA3") (pin "9") (pinfunction "9_9") (pintype "passive"))
      (node (ref "IC12") (pin "12") (pinfunction "8Q_12") (pintype "tri_state"))
    )
    (net (code "76") (name "LD24") (class "Default")
      (node (ref "DATA4") (pin "1") (pinfunction "1_1") (pintype "passive"))
      (node (ref "IC16") (pin "19") (pinfunction "1Q_19") (pintype "tri_state"))
    )
    (net (code "77") (name "LD25") (class "Default")
      (node (ref "DATA4") (pin "2") (pinfunction "2_2") (pintype "passive"))
      (node (ref "IC16") (pin "18") (pinfunction "2Q_18") (pintype "tri_state"))
    )
    (net (code "78") (name "LD26") (class "Default")
      (node (ref "DATA4") (pin "3") (pinfunction "3_3") (pintype "passive"))
      (node (ref "IC16") (pin "17") (pinfunction "3Q_17") (pintype "tri_state"))
    )
    (net (code "79") (name "LD27") (class "Default")
      (node (ref "DATA4") (pin "4") (pinfunction "4_4") (pintype "passive"))
      (node (ref "IC16") (pin "16") (pinfunction "4Q_16") (pintype "tri_state"))
    )
    (net (code "80") (name "LD28") (class "Default")
      (node (ref "DATA4") (pin "8") (pinfunction "8_8") (pintype "passive"))
      (node (ref "IC16") (pin "15") (pinfunction "5Q_15") (pintype "tri_state"))
    )
    (net (code "81") (name "LD29") (class "Default")
      (node (ref "DATA4") (pin "7") (pinfunction "7_7") (pintype "passive"))
      (node (ref "IC16") (pin "14") (pinfunction "6Q_14") (pintype "tri_state"))
    )
    (net (code "82") (name "LD30") (class "Default")
      (node (ref "DATA4") (pin "10") (pinfunction "10_10") (pintype "passive"))
      (node (ref "IC16") (pin "13") (pinfunction "7Q_13") (pintype "tri_state"))
    )
    (net (code "83") (name "LD31") (class "Default")
      (node (ref "DATA4") (pin "9") (pinfunction "9_9") (pintype "passive"))
      (node (ref "IC16") (pin "12") (pinfunction "8Q_12") (pintype "tri_state"))
    )
    (net (code "84") (name "LDR") (class "Default")
      (node (ref "CTRL") (pin "8") (pinfunction "8_8") (pintype "passive"))
      (node (ref "IC1") (pin "17") (pinfunction "3Q_17") (pintype "tri_state"))
    )
    (net (code "85") (name "LFC0") (class "Default")
      (node (ref "IC14") (pin "16") (pinfunction "Y2_16") (pintype "tri_state"))
      (node (ref "STATE") (pin "11") (pinfunction "11_11") (pintype "passive"))
    )
    (net (code "86") (name "LFC1") (class "Default")
      (node (ref "IC14") (pin "14") (pinfunction "Y3_14") (pintype "tri_state"))
      (node (ref "STATE") (pin "14") (pinfunction "14_14") (pintype "passive"))
    )
    (net (code "87") (name "LFC2") (class "Default")
      (node (ref "IC15") (pin "18") (pinfunction "Y1_18") (pintype "tri_state"))
      (node (ref "STATE") (pin "13") (pinfunction "13_13") (pintype "passive"))
    )
    (net (code "88") (name "LHLT") (class "Default")
      (node (ref "IC15") (pin "5") (pinfunction "Y3_5") (pintype "tri_state"))
      (node (ref "STATE") (pin "2") (pinfunction "2_2") (pintype "passive"))
    )
    (net (code "89") (name "LIAC") (class "Default")
      (node (ref "IC14") (pin "7") (pinfunction "Y2_7") (pintype "tri_state"))
      (node (ref "STATE") (pin "12") (pinfunction "12_12") (pintype "passive"))
    )
    (net (code "90") (name "LLDS") (class "Default")
      (node (ref "IC15") (pin "14") (pinfunction "Y3_14") (pintype "tri_state"))
      (node (ref "STATE") (pin "3") (pinfunction "3_3") (pintype "passive"))
    )
    (net (code "91") (name "LMEM") (class "Default")
      (node (ref "CTRL") (pin "10") (pinfunction "10_10") (pintype "passive"))
      (node (ref "IC1") (pin "16") (pinfunction "4Q_16") (pintype "tri_state"))
    )
    (net (code "92") (name "LR0") (class "Default")
      (node (ref "CTRL") (pin "1") (pinfunction "1_1") (pintype "passive"))
      (node (ref "IC1") (pin "19") (pinfunction "1Q_19") (pintype "tri_state"))
    )
    (net (code "93") (name "LR1") (class "Default")
      (node (ref "CTRL") (pin "2") (pinfunction "2_2") (pintype "passive"))
      (node (ref "IC1") (pin "18") (pinfunction "2Q_18") (pintype "tri_state"))
    )
    (net (code "94") (name "LR2") (class "Default")
      (node (ref "CTRL") (pin "4") (pinfunction "4_4") (pintype "passive"))
      (node (ref "IC1") (pin "12") (pinfunction "8Q_12") (pintype "tri_state"))
    )
    (net (code "95") (name "LRD") (class "Default")
      (node (ref "IC15") (pin "3") (pinfunction "Y4_3") (pintype "tri_state"))
      (node (ref "STATE") (pin "5") (pinfunction "5_5") (pintype "passive"))
    )
    (net (code "96") (name "LRST") (class "Default")
      (node (ref "IC15") (pin "9") (pinfunction "Y1_9") (pintype "tri_state"))
      (node (ref "STATE") (pin "1") (pinfunction "1_1") (pintype "passive"))
    )
    (net (code "97") (name "LSP") (class "Default")
      (node (ref "CTRL") (pin "3") (pinfunction "3_3") (pintype "passive"))
      (node (ref "IC1") (pin "14") (pinfunction "6Q_14") (pintype "tri_state"))
    )
    (net (code "98") (name "LSUP") (class "Default")
      (node (ref "IC14") (pin "3") (pinfunction "Y4_3") (pintype "tri_state"))
      (node (ref "STATE") (pin "9") (pinfunction "9_9") (pintype "passive"))
    )
    (net (code "99") (name "LSYN") (class "Default")
      (node (ref "IC15") (pin "16") (pinfunction "Y2_16") (pintype "tri_state"))
      (node (ref "STATE") (pin "8") (pinfunction "8_8") (pintype "passive"))
    )
    (net (code "100") (name "LUDS") (class "Default")
      (node (ref "IC15") (pin "12") (pinfunction "Y4_12") (pintype "tri_state"))
      (node (ref "STATE") (pin "4") (pinfunction "4_4") (pintype "passive"))
    )
    (net (code "101") (name "LUSR") (class "Default")
      (node (ref "IC14") (pin "5") (pinfunction "Y3_5") (pintype "tri_state"))
      (node (ref "STATE") (pin "10") (pinfunction "10_10") (pintype "passive"))
    )
    (net (code "102") (name "LWR") (class "Default")
      (node (ref "IC15") (pin "17") (pinfunction "A4_17") (pintype "input"))
      (node (ref "IC15") (pin "7") (pinfunction "Y2_7") (pintype "tri_state"))
      (node (ref "STATE") (pin "6") (pinfunction "6_6") (pintype "passive"))
    )
    (net (code "103") (name "Net-(IC13B-CLK)") (class "Default")
      (node (ref "IC13") (pin "11") (pinfunction "CLK_11") (pintype "input"))
      (node (ref "STP") (pin "3") (pinfunction "3_3") (pintype "passive"))
    )
    (net (code "104") (name "Net-(IC13B-CLR)") (class "Default")
      (node (ref "IC13") (pin "13") (pinfunction "CLR_13") (pintype "input"))
      (node (ref "STP") (pin "1") (pinfunction "1_1") (pintype "passive"))
    )
    (net (code "105") (name "Net-(IC13B-~{Q})") (class "Default")
      (node (ref "IC13") (pin "8") (pinfunction "~{Q}_8") (pintype "output"))
      (node (ref "STP") (pin "2") (pinfunction "2_2") (pintype "passive"))
    )
    (net (code "106") (name "Net-(IC14A-A2)") (class "Default")
      (node (ref "IC14") (pin "18") (pinfunction "Y1_18") (pintype "tri_state"))
      (node (ref "IC14") (pin "4") (pinfunction "A2_4") (pintype "input"))
    )
    (net (code "107") (name "Net-(IC14A-A3)") (class "Default")
      (node (ref "IC14") (pin "12") (pinfunction "Y4_12") (pintype "tri_state"))
      (node (ref "IC14") (pin "6") (pinfunction "A3_6") (pintype "input"))
    )
    (net (code "108") (name "Net-(IC14B-Y1)") (class "Default")
      (node (ref "IC14") (pin "9") (pinfunction "Y1_9") (pintype "tri_state"))
      (node (ref "IC15") (pin "2") (pinfunction "A1_2") (pintype "input"))
    )
    (net (code "109") (name "Net-(IC15B-A3)") (class "Default")
      (node (ref "!HALT") (pin "1") (pinfunction "1_1") (pintype "passive"))
      (node (ref "IC15") (pin "15") (pinfunction "A3_15") (pintype "input"))
      (node (ref "R1") (pin "2") (pinfunction "2_2") (pintype "passive"))
    )
    (net (code "110") (name "R{slash}~{WB}") (class "Default")
      (node (ref "IC10") (pin "6") (pinfunction "G1_6") (pintype "input"))
      (node (ref "IC11") (pin "11") (pinfunction "OE_11") (pintype "input"))
      (node (ref "IC15") (pin "13") (pinfunction "A2_13") (pintype "input"))
      (node (ref "IC9") (pin "5") (pinfunction "G2B_5") (pintype "input"))
      (node (ref "JP3") (pin "1") (pinfunction "1_1") (pintype "passive"))
    )
    (net (code "111") (name "VCC") (class "Default")
      (node (ref "C1") (pin "1") (pinfunction "1_1") (pintype "passive"))
      (node (ref "C10") (pin "1") (pinfunction "1_1") (pintype "passive"))
      (node (ref "C11") (pin "1") (pinfunction "1_1") (pintype "passive"))
      (node (ref "C12") (pin "1") (pinfunction "1_1") (pintype "passive"))
      (node (ref "C13") (pin "+") (pinfunction "+_+") (pintype "passive"))
      (node (ref "C14") (pin "1") (pinfunction "1_1") (pintype "passive"))
      (node (ref "C15") (pin "1") (pinfunction "1_1") (pintype "passive"))
      (node (ref "C16") (pin "1") (pinfunction "1_1") (pintype "passive"))
      (node (ref "C2") (pin "1") (pinfunction "1_1") (pintype "passive"))
      (node (ref "C3") (pin "1") (pinfunction "1_1") (pintype "passive"))
      (node (ref "C4") (pin "1") (pinfunction "1_1") (pintype "passive"))
      (node (ref "C5") (pin "1") (pinfunction "1_1") (pintype "passive"))
      (node (ref "C6") (pin "1") (pinfunction "1_1") (pintype "passive"))
      (node (ref "C7") (pin "1") (pinfunction "1_1") (pintype "passive"))
      (node (ref "C8") (pin "1") (pinfunction "1_1") (pintype "passive"))
      (node (ref "C9") (pin "1") (pinfunction "1_1") (pintype "passive"))
      (node (ref "IC11") (pin "20") (pinfunction "VCC_20") (pintype "power_in"))
      (node (ref "IC13") (pin "10") (pinfunction "PRE_10") (pintype "input"))
      (node (ref "IC13") (pin "12") (pinfunction "D_12") (pintype "input"))
      (node (ref "JP8") (pin "2") (pinfunction "2_2") (pintype "passive"))
      (node (ref "JP8") (pin "4") (pinfunction "4_4") (pintype "passive"))
      (node (ref "R1") (pin "1") (pinfunction "1_1") (pintype "passive"))
    )
    (net (code "112") (name "unconnected-(IC11-I5-Pad6)") (class "Default")
      (node (ref "IC11") (pin "6") (pinfunction "I5_6") (pintype "input"))
    )
    (net (code "113") (name "unconnected-(IC11-I6-Pad7)") (class "Default")
      (node (ref "IC11") (pin "7") (pinfunction "I6_7") (pintype "input"))
    )
    (net (code "114") (name "unconnected-(IC11-I7-Pad8)") (class "Default")
      (node (ref "IC11") (pin "8") (pinfunction "I7_8") (pintype "input"))
    )
    (net (code "115") (name "unconnected-(IC11-O2-Pad18)") (class "Default")
      (node (ref "IC11") (pin "18") (pinfunction "O2_18") (pintype "output"))
    )
    (net (code "116") (name "unconnected-(IC11-O6-Pad14)") (class "Default")
      (node (ref "IC11") (pin "14") (pinfunction "O6_14") (pintype "output"))
    )
    (net (code "117") (name "unconnected-(IC11-O8-Pad12)") (class "Default")
      (node (ref "IC11") (pin "12") (pinfunction "O8_12") (pintype "output"))
    )
    (net (code "118") (name "unconnected-(IC13B-Q-Pad9)") (class "Default")
      (node (ref "IC13") (pin "9") (pinfunction "Q_9") (pintype "output"))
    )
    (net (code "119") (name "unconnected-(JP2-Pad10)") (class "Default")
      (node (ref "JP2") (pin "10") (pinfunction "10_10") (pintype "passive"))
    )
    (net (code "120") (name "unconnected-(JP7-Pad3)") (class "Default")
      (node (ref "JP7") (pin "3") (pinfunction "3_3") (pintype "passive"))
    )
    (net (code "121") (name "unconnected-(JP9-Pad4)") (class "Default")
      (node (ref "JP9") (pin "4") (pinfunction "4_4") (pintype "passive"))
    )
    (net (code "122") (name "unconnected-(JP9-Pad5)") (class "Default")
      (node (ref "JP9") (pin "5") (pinfunction "5_5") (pintype "passive"))
    )
    (net (code "123") (name "unconnected-(JP9-Pad14)") (class "Default")
      (node (ref "JP9") (pin "14") (pinfunction "14_14") (pintype "passive"))
    )
    (net (code "124") (name "~{ASB}") (class "Default")
      (node (ref "JP1") (pin "2") (pinfunction "2_2") (pintype "passive"))
    )
    (net (code "125") (name "~{BERRB}") (class "Default")
      (node (ref "JP1") (pin "1") (pinfunction "1_1") (pintype "passive"))
    )
    (net (code "126") (name "~{CLRTOGGL}") (class "Default")
      (node (ref "IC10") (pin "10") (pinfunction "Y5_10") (pintype "output"))
      (node (ref "JP9") (pin "11") (pinfunction "11_11") (pintype "passive"))
    )
    (net (code "127") (name "~{CONSEL}") (class "Default")
      (node (ref "IC10") (pin "5") (pinfunction "G2B_5") (pintype "input"))
      (node (ref "IC11") (pin "5") (pinfunction "I4_5") (pintype "input"))
      (node (ref "IC9") (pin "4") (pinfunction "G2A_4") (pintype "input"))
      (node (ref "JP9") (pin "12") (pinfunction "12_12") (pintype "passive"))
    )
    (net (code "128") (name "~{CPUOUT}") (class "Default")
      (node (ref "IC13") (pin "5") (pinfunction "Q_5") (pintype "output"))
      (node (ref "IC2") (pin "1") (pinfunction "OC_1") (pintype "input"))
      (node (ref "IC8") (pin "1") (pinfunction "OC_1") (pintype "input"))
      (node (ref "JP7") (pin "1") (pinfunction "1_1") (pintype "passive"))
    )
    (net (code "129") (name "~{DATA0ENA}") (class "Default")
      (node (ref "JP3") (pin "10") (pinfunction "10_10") (pintype "passive"))
      (node (ref "JPD") (pin "2") (pinfunction "2_2") (pintype "passive"))
    )
    (net (code "130") (name "~{DTACK}") (class "Default")
      (node (ref "DT") (pin "1") (pinfunction "1_1") (pintype "passive"))
      (node (ref "IC11") (pin "9") (pinfunction "I8_9") (pintype "input"))
    )
    (net (code "131") (name "~{IAC}") (class "Default")
      (node (ref "IC14") (pin "13") (pinfunction "A2_13") (pintype "input"))
      (node (ref "JP9") (pin "6") (pinfunction "6_6") (pintype "passive"))
    )
    (net (code "132") (name "~{LATCHD0}") (class "Default")
      (node (ref "IC11") (pin "15") (pinfunction "O5_15") (pintype "output"))
      (node (ref "IC8") (pin "11") (pinfunction "CLK_11") (pintype "input"))
    )
    (net (code "133") (name "~{LATCHD8}") (class "Default")
      (node (ref "IC11") (pin "17") (pinfunction "O3_17") (pintype "output"))
      (node (ref "IC2") (pin "11") (pinfunction "CLK_11") (pintype "input"))
    )
    (net (code "134") (name "~{LDSB}") (class "Default")
      (node (ref "IC11") (pin "16") (pinfunction "O4_16") (pintype "output"))
      (node (ref "IC15") (pin "6") (pinfunction "A3_6") (pintype "input"))
      (node (ref "JP1") (pin "4") (pinfunction "4_4") (pintype "passive"))
    )
    (net (code "135") (name "~{RDSWR00}") (class "Default")
      (node (ref "IC10") (pin "15") (pinfunction "Y0_15") (pintype "output"))
      (node (ref "JP9") (pin "2") (pinfunction "2_2") (pintype "passive"))
    )
    (net (code "136") (name "~{RDSWR08}") (class "Default")
      (node (ref "IC10") (pin "14") (pinfunction "Y1_14") (pintype "output"))
      (node (ref "JP9") (pin "7") (pinfunction "7_7") (pintype "passive"))
    )
    (net (code "137") (name "~{RDSWR16}") (class "Default")
      (node (ref "IC10") (pin "13") (pinfunction "Y2_13") (pintype "output"))
      (node (ref "JP9") (pin "1") (pinfunction "1_1") (pintype "passive"))
    )
    (net (code "138") (name "~{RDSWR24}") (class "Default")
      (node (ref "IC10") (pin "12") (pinfunction "Y3_12") (pintype "output"))
      (node (ref "JP9") (pin "3") (pinfunction "3_3") (pintype "passive"))
    )
    (net (code "139") (name "~{RDTOGGL}") (class "Default")
      (node (ref "IC10") (pin "11") (pinfunction "Y4_11") (pintype "output"))
      (node (ref "JP9") (pin "9") (pinfunction "9_9") (pintype "passive"))
    )
    (net (code "140") (name "~{RESET}") (class "Default")
      (node (ref "IC13") (pin "3") (pinfunction "CLK_3") (pintype "input"))
      (node (ref "IC15") (pin "11") (pinfunction "A1_11") (pintype "input"))
      (node (ref "JP9") (pin "13") (pinfunction "13_13") (pintype "passive"))
    )
    (net (code "141") (name "~{SELCPUDAT}") (class "Default")
      (node (ref "IC10") (pin "7") (pinfunction "Y7_7") (pintype "output"))
      (node (ref "IC13") (pin "1") (pinfunction "CLR_1") (pintype "input"))
    )
    (net (code "142") (name "~{SELUSRDAT}") (class "Default")
      (node (ref "IC10") (pin "9") (pinfunction "Y6_9") (pintype "output"))
      (node (ref "IC13") (pin "4") (pinfunction "PRE_4") (pintype "input"))
    )
    (net (code "143") (name "~{SUP}") (class "Default")
      (node (ref "IC14") (pin "17") (pinfunction "A4_17") (pintype "input"))
      (node (ref "JP9") (pin "10") (pinfunction "10_10") (pintype "passive"))
    )
    (net (code "144") (name "~{UDSB}") (class "Default")
      (node (ref "IC11") (pin "13") (pinfunction "O7_13") (pintype "output"))
      (node (ref "IC15") (pin "8") (pinfunction "A4_8") (pintype "input"))
      (node (ref "JP1") (pin "3") (pinfunction "3_3") (pintype "passive"))
    )
    (net (code "145") (name "~{USROUT}") (class "Default")
      (node (ref "IC12") (pin "1") (pinfunction "OC_1") (pintype "input"))
      (node (ref "IC13") (pin "6") (pinfunction "~{Q}_6") (pintype "output"))
      (node (ref "IC16") (pin "1") (pinfunction "OC_1") (pintype "input"))
      (node (ref "IC3") (pin "1") (pinfunction "OC_1") (pintype "input"))
      (node (ref "IC4") (pin "1") (pinfunction "OC_1") (pintype "input"))
      (node (ref "IC5") (pin "1") (pinfunction "OC_1") (pintype "input"))
      (node (ref "IC6") (pin "1") (pinfunction "OC_1") (pintype "input"))
      (node (ref "IC7") (pin "1") (pinfunction "OC_1") (pintype "input"))
    )
    (net (code "146") (name "~{USR}") (class "Default")
      (node (ref "IC14") (pin "15") (pinfunction "A3_15") (pintype "input"))
      (node (ref "JP9") (pin "8") (pinfunction "8_8") (pintype "passive"))
    )
    (net (code "147") (name "~{VPAB}") (class "Default")
      (node (ref "IC15") (pin "4") (pinfunction "A2_4") (pintype "input"))
      (node (ref "JP1") (pin "8") (pinfunction "8_8") (pintype "passive"))
    )
    (net (code "148") (name "~{WRCTRLED}") (class "Default")
      (node (ref "IC1") (pin "11") (pinfunction "CLK_11") (pintype "input"))
      (node (ref "IC9") (pin "11") (pinfunction "Y4_11") (pintype "output"))
    )
    (net (code "149") (name "~{WRUSRA00}") (class "Default")
      (node (ref "IC4") (pin "11") (pinfunction "CLK_11") (pintype "input"))
      (node (ref "IC9") (pin "10") (pinfunction "Y5_10") (pintype "output"))
    )
    (net (code "150") (name "~{WRUSRA08}") (class "Default")
      (node (ref "IC5") (pin "11") (pinfunction "CLK_11") (pintype "input"))
      (node (ref "IC9") (pin "9") (pinfunction "Y6_9") (pintype "output"))
    )
    (net (code "151") (name "~{WRUSRA16}") (class "Default")
      (node (ref "IC6") (pin "11") (pinfunction "CLK_11") (pintype "input"))
      (node (ref "IC9") (pin "7") (pinfunction "Y7_7") (pintype "output"))
    )
    (net (code "152") (name "~{WRUSRD00}") (class "Default")
      (node (ref "IC7") (pin "11") (pinfunction "CLK_11") (pintype "input"))
      (node (ref "IC9") (pin "15") (pinfunction "Y0_15") (pintype "output"))
    )
    (net (code "153") (name "~{WRUSRD08}") (class "Default")
      (node (ref "IC3") (pin "11") (pinfunction "CLK_11") (pintype "input"))
      (node (ref "IC9") (pin "14") (pinfunction "Y1_14") (pintype "output"))
    )
    (net (code "154") (name "~{WRUSRD16}") (class "Default")
      (node (ref "IC12") (pin "11") (pinfunction "CLK_11") (pintype "input"))
      (node (ref "IC9") (pin "13") (pinfunction "Y2_13") (pintype "output"))
    )
    (net (code "155") (name "~{WRUSRD24}") (class "Default")
      (node (ref "IC16") (pin "11") (pinfunction "CLK_11") (pintype "input"))
      (node (ref "IC9") (pin "12") (pinfunction "Y3_12") (pintype "output"))
    )
  )
)
